# F411CEU6.net
KiCad netlist of a schematic drawn in Altium Designer
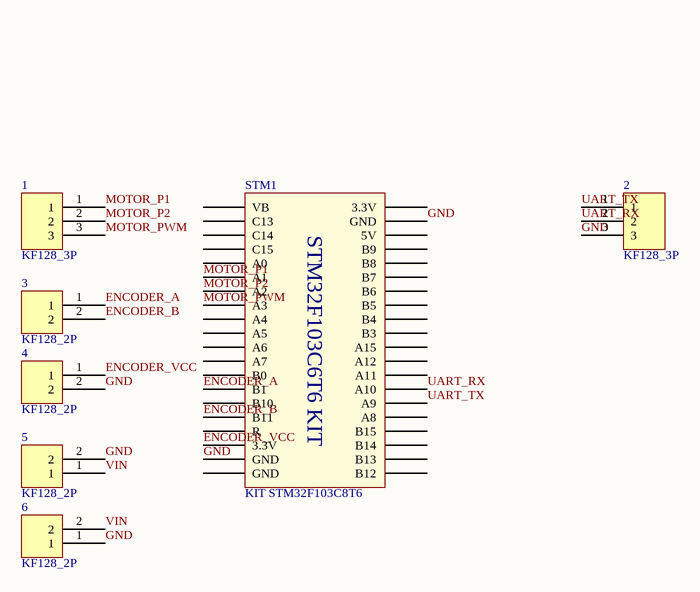
[diagram p0: F411CEU6.SchDoc]

(export (version "E")
  (design (tool "Eeschema 10.0.6"))
  (components
    (comp (ref "1")
      (value "KF128_3P")
      (footprint "KF128_3P")
      (description "KF128 - pin spacing 3.81mm - 3P")
      (libsource (lib "") (part "KF128_3P_1"))
    )
    (comp (ref "2")
      (value "KF128_3P")
      (footprint "KF128_3P")
      (description "KF128 - pin spacing 3.81mm - 3P")
      (libsource (lib "KF128_3P_381mm") (part "KF128_3P"))
    )
    (comp (ref "3")
      (value "KF128_2P")
      (footprint "KF128_2P")
      (description "KF128 - pin spacing 3.81mm - 2P")
      (libsource (lib "KF128_3P_381mm") (part "KF128_2P"))
    )
    (comp (ref "4")
      (value "KF128_2P")
      (footprint "KF128_2P")
      (description "KF128 - pin spacing 3.81mm - 2P")
      (libsource (lib "KF128_3P_381mm") (part "KF128_2P"))
    )
    (comp (ref "5")
      (value "KF128_2P")
      (footprint "KF128_2P")
      (description "KF128 - pin spacing 3.81mm - 2P")
      (libsource (lib "") (part "KF128_2P_1"))
    )
    (comp (ref "6")
      (value "KF128_2P")
      (footprint "KF128_2P")
      (description "KF128 - pin spacing 3.81mm - 2P")
      (libsource (lib "") (part "KF128_2P_1"))
    )
    (comp (ref "STM1")
      (value "KIT STM32F103C8T6")
      (footprint "STM32F103 KIT")
      (description "KIT STM32F103C8T6 Bluepill")
      (libsource (lib "Altium_Lib_by_KhueNguyenCreator") (part "STM32f103 Bluepill"))
    )
  )
  (nets
    (net (code "1") (name "/ENCODER_A") (class "Default")
      (node (ref "3") (pin "1") (pinfunction "1_1") (pintype "passive"))
      (node (ref "STM1") (pin "34") (pinfunction "B1_34") (pintype "passive"))
    )
    (net (code "2") (name "/ENCODER_B") (class "Default")
      (node (ref "3") (pin "2") (pinfunction "2_2") (pintype "passive"))
      (node (ref "STM1") (pin "36") (pinfunction "B11_36") (pintype "passive"))
    )
    (net (code "3") (name "/ENCODER_VCC") (class "Default")
      (node (ref "4") (pin "1") (pinfunction "1_1") (pintype "passive"))
      (node (ref "STM1") (pin "38") (pinfunction "3.3V_38") (pintype "passive"))
    )
    (net (code "4") (name "/GND") (class "Default")
      (node (ref "2") (pin "3") (pinfunction "3_3") (pintype "passive"))
      (node (ref "4") (pin "2") (pinfunction "2_2") (pintype "passive"))
      (node (ref "5") (pin "2") (pinfunction "2_2") (pintype "passive"))
      (node (ref "6") (pin "1") (pinfunction "1_1") (pintype "passive"))
      (node (ref "STM1") (pin "19") (pinfunction "GND_19") (pintype "passive"))
      (node (ref "STM1") (pin "39") (pinfunction "GND_39") (pintype "passive"))
    )
    (net (code "5") (name "/MOTOR_P1") (class "Default")
      (node (ref "1") (pin "1") (pinfunction "1_1") (pintype "passive"))
      (node (ref "STM1") (pin "26") (pinfunction "A1_26") (pintype "passive"))
    )
    (net (code "6") (name "/MOTOR_P2") (class "Default")
      (node (ref "1") (pin "2") (pinfunction "2_2") (pintype "passive"))
      (node (ref "STM1") (pin "27") (pinfunction "A2_27") (pintype "passive"))
    )
    (net (code "7") (name "/MOTOR_PWM") (class "Default")
      (node (ref "1") (pin "3") (pinfunction "3_3") (pintype "passive"))
      (node (ref "STM1") (pin "28") (pinfunction "A3_28") (pintype "passive"))
    )
    (net (code "8") (name "/UART_RX") (class "Default")
      (node (ref "2") (pin "2") (pinfunction "2_2") (pintype "passive"))
      (node (ref "STM1") (pin "7") (pinfunction "A10_7") (pintype "passive"))
    )
    (net (code "9") (name "/UART_TX") (class "Default")
      (node (ref "2") (pin "1") (pinfunction "1_1") (pintype "passive"))
      (node (ref "STM1") (pin "6") (pinfunction "A9_6") (pintype "passive"))
    )
    (net (code "10") (name "/VIN") (class "Default")
      (node (ref "5") (pin "1") (pinfunction "1_1") (pintype "passive"))
      (node (ref "6") (pin "2") (pinfunction "2_2") (pintype "passive"))
    )
    (net (code "11") (name "unconnected-(STM1-3.3V-Pad20)") (class "Default")
      (node (ref "STM1") (pin "20") (pinfunction "3.3V_20") (pintype "passive"))
    )
    (net (code "12") (name "unconnected-(STM1-5V-Pad18)") (class "Default")
      (node (ref "STM1") (pin "18") (pinfunction "5V_18") (pintype "passive"))
    )
    (net (code "13") (name "unconnected-(STM1-A0-Pad25)") (class "Default")
      (node (ref "STM1") (pin "25") (pinfunction "A0_25") (pintype "passive"))
    )
    (net (code "14") (name "unconnected-(STM1-A4-Pad29)") (class "Default")
      (node (ref "STM1") (pin "29") (pinfunction "A4_29") (pintype "passive"))
    )
    (net (code "15") (name "unconnected-(STM1-A5-Pad30)") (class "Default")
      (node (ref "STM1") (pin "30") (pinfunction "A5_30") (pintype "passive"))
    )
    (net (code "16") (name "unconnected-(STM1-A6-Pad31)") (class "Default")
      (node (ref "STM1") (pin "31") (pinfunction "A6_31") (pintype "passive"))
    )
    (net (code "17") (name "unconnected-(STM1-A7-Pad32)") (class "Default")
      (node (ref "STM1") (pin "32") (pinfunction "A7_32") (pintype "passive"))
    )
    (net (code "18") (name "unconnected-(STM1-A8-Pad5)") (class "Default")
      (node (ref "STM1") (pin "5") (pinfunction "A8_5") (pintype "passive"))
    )
    (net (code "19") (name "unconnected-(STM1-A11-Pad8)") (class "Default")
      (node (ref "STM1") (pin "8") (pinfunction "A11_8") (pintype "passive"))
    )
    (net (code "20") (name "unconnected-(STM1-A12-Pad9)") (class "Default")
      (node (ref "STM1") (pin "9") (pinfunction "A12_9") (pintype "passive"))
    )
    (net (code "21") (name "unconnected-(STM1-A15-Pad10)") (class "Default")
      (node (ref "STM1") (pin "10") (pinfunction "A15_10") (pintype "passive"))
    )
    (net (code "22") (name "unconnected-(STM1-B0-Pad33)") (class "Default")
      (node (ref "STM1") (pin "33") (pinfunction "B0_33") (pintype "passive"))
    )
    (net (code "23") (name "unconnected-(STM1-B3-Pad11)") (class "Default")
      (node (ref "STM1") (pin "11") (pinfunction "B3_11") (pintype "passive"))
    )
    (net (code "24") (name "unconnected-(STM1-B4-Pad12)") (class "Default")
      (node (ref "STM1") (pin "12") (pinfunction "B4_12") (pintype "passive"))
    )
    (net (code "25") (name "unconnected-(STM1-B5-Pad13)") (class "Default")
      (node (ref "STM1") (pin "13") (pinfunction "B5_13") (pintype "passive"))
    )
    (net (code "26") (name "unconnected-(STM1-B6-Pad14)") (class "Default")
      (node (ref "STM1") (pin "14") (pinfunction "B6_14") (pintype "passive"))
    )
    (net (code "27") (name "unconnected-(STM1-B7-Pad15)") (class "Default")
      (node (ref "STM1") (pin "15") (pinfunction "B7_15") (pintype "passive"))
    )
    (net (code "28") (name "unconnected-(STM1-B8-Pad16)") (class "Default")
      (node (ref "STM1") (pin "16") (pinfunction "B8_16") (pintype "passive"))
    )
    (net (code "29") (name "unconnected-(STM1-B9-Pad17)") (class "Default")
      (node (ref "STM1") (pin "17") (pinfunction "B9_17") (pintype "passive"))
    )
    (net (code "30") (name "unconnected-(STM1-B10-Pad35)") (class "Default")
      (node (ref "STM1") (pin "35") (pinfunction "B10_35") (pintype "passive"))
    )
    (net (code "31") (name "unconnected-(STM1-B12-Pad1)") (class "Default")
      (node (ref "STM1") (pin "1") (pinfunction "B12_1") (pintype "passive"))
    )
    (net (code "32") (name "unconnected-(STM1-B13-Pad2)") (class "Default")
      (node (ref "STM1") (pin "2") (pinfunction "B13_2") (pintype "passive"))
    )
    (net (code "33") (name "unconnected-(STM1-B14-Pad3)") (class "Default")
      (node (ref "STM1") (pin "3") (pinfunction "B14_3") (pintype "passive"))
    )
    (net (code "34") (name "unconnected-(STM1-B15-Pad4)") (class "Default")
      (node (ref "STM1") (pin "4") (pinfunction "B15_4") (pintype "passive"))
    )
    (net (code "35") (name "unconnected-(STM1-C13-Pad22)") (class "Default")
      (node (ref "STM1") (pin "22") (pinfunction "C13_22") (pintype "passive"))
    )
    (net (code "36") (name "unconnected-(STM1-C14-Pad23)") (class "Default")
      (node (ref "STM1") (pin "23") (pinfunction "C14_23") (pintype "passive"))
    )
    (net (code "37") (name "unconnected-(STM1-C15-Pad24)") (class "Default")
      (node (ref "STM1") (pin "24") (pinfunction "C15_24") (pintype "passive"))
    )
    (net (code "38") (name "unconnected-(STM1-GND-Pad40)") (class "Default")
      (node (ref "STM1") (pin "40") (pinfunction "GND_40") (pintype "passive"))
    )
    (net (code "39") (name "unconnected-(STM1-R-Pad37)") (class "Default")
      (node (ref "STM1") (pin "37") (pinfunction "R_37") (pintype "passive"))
    )
    (net (code "40") (name "unconnected-(STM1-VB-Pad21)") (class "Default")
      (node (ref "STM1") (pin "21") (pinfunction "VB_21") (pintype "passive"))
    )
  )
)
